# Timer.net
KiCad netlist of a schematic drawn in Altium Designer
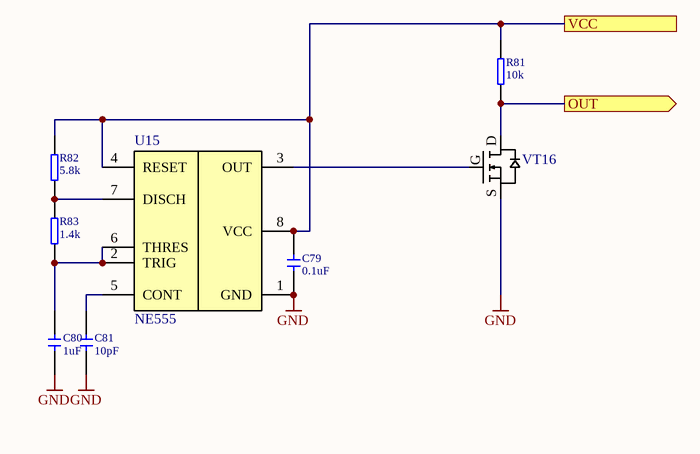
[diagram p0: Timer.SchDoc]

(export (version "E")
  (design (tool "Eeschema 10.0.6"))
  (components
    (comp (ref "C79")
      (value "0.1uF")
      (footprint "CERCAP 0402")
      (description "Capacitor")
      (fields (field (name "VOLTAGE") "50V") (field (name "Comment") "CERCAP 0402 0.1uF 50V X7R"))
      (libsource (lib "!main") (part "!Capacitor"))
    )
    (comp (ref "C80")
      (value "1uF")
      (footprint "CERCAP 0603")
      (description "Capacitor")
      (fields (field (name "VOLTAGE") "50V") (field (name "Comment") "CERCAP 0603 1uF 50V X7R"))
      (libsource (lib "!main") (part "!Capacitor"))
    )
    (comp (ref "C81")
      (value "10pF")
      (footprint "CERCAP 0402")
      (description "Capacitor")
      (fields (field (name "VOLTAGE") "50V") (field (name "Comment") "CERCAP 0402 10pF 50V X7R"))
      (libsource (lib "!main") (part "!Capacitor"))
    )
    (comp (ref "R81")
      (value "10k")
      (footprint "RES 0402")
      (description "Resistor")
      (fields (field (name "Comment") "RES 0402 10k"))
      (libsource (lib "!main") (part "!Resistor"))
    )
    (comp (ref "R82")
      (value "5.8k")
      (footprint "RES 0402")
      (description "Resistor")
      (fields (field (name "Comment") "RES 0402 5.8k"))
      (libsource (lib "!main") (part "!Resistor"))
    )
    (comp (ref "R83")
      (value "1.4k")
      (footprint "RES 0402")
      (description "Resistor")
      (fields (field (name "Comment") "RES 0402 1.4k"))
      (libsource (lib "!main") (part "!Resistor"))
    )
    (comp (ref "U15")
      (value "NE555")
      (footprint "SO-8")
      (description "555 timer")
      (libsource (lib "CPLD_FPGA_logic") (part "NE555"))
    )
    (comp (ref "VT16")
      (value "2N7002")
      (footprint "SOT23-3")
      (description "generic N mosfet")
      (libsource (lib "transistors") (part "!Generic N MOSFET"))
    )
  )
  (nets
    (net (code "1") (name "/OUT") (class "Default")
      (node (ref "R81") (pin "1") (pinfunction "11_1") (pintype "passive"))
      (node (ref "VT16") (pin "D6") (pintype "passive"))
    )
    (net (code "2") (name "/VCC") (class "Default")
      (node (ref "C79") (pin "2") (pintype "passive"))
      (node (ref "R81") (pin "2") (pinfunction "12_2") (pintype "passive"))
      (node (ref "R82") (pin "2") (pinfunction "12_2") (pintype "passive"))
      (node (ref "U15") (pin "4") (pinfunction "RESET_4") (pintype "passive"))
      (node (ref "U15") (pin "8") (pinfunction "VCC_8") (pintype "passive"))
    )
    (net (code "3") (name "GND") (class "Default")
      (node (ref "C79") (pin "1") (pintype "passive"))
      (node (ref "C80") (pin "1") (pintype "passive"))
      (node (ref "C81") (pin "1") (pintype "passive"))
      (node (ref "U15") (pin "1") (pinfunction "GND_1") (pintype "passive"))
      (node (ref "VT16") (pin "S1") (pintype "passive"))
    )
    (net (code "4") (name "Net-(R82-11)") (class "Default")
      (node (ref "R82") (pin "1") (pinfunction "11_1") (pintype "passive"))
      (node (ref "R83") (pin "2") (pinfunction "12_2") (pintype "passive"))
      (node (ref "U15") (pin "7") (pinfunction "DISCH_7") (pintype "passive"))
    )
    (net (code "5") (name "Net-(R83-11)") (class "Default")
      (node (ref "C80") (pin "2") (pintype "passive"))
      (node (ref "R83") (pin "1") (pinfunction "11_1") (pintype "passive"))
      (node (ref "U15") (pin "2") (pinfunction "TRIG_2") (pintype "passive"))
      (node (ref "U15") (pin "6") (pinfunction "THRES_6") (pintype "passive"))
    )
    (net (code "6") (name "Net-(U15-CONT)") (class "Default")
      (node (ref "C81") (pin "2") (pintype "passive"))
      (node (ref "U15") (pin "5") (pinfunction "CONT_5") (pintype "passive"))
    )
    (net (code "7") (name "Net-(U15-OUT)") (class "Default")
      (node (ref "U15") (pin "3") (pinfunction "OUT_3") (pintype "passive"))
      (node (ref "VT16") (pin "G2") (pintype "passive"))
    )
  )
)
